# adapter_nucleo_f446re.net
KiCad netlist of a schematic drawn in EAGLE
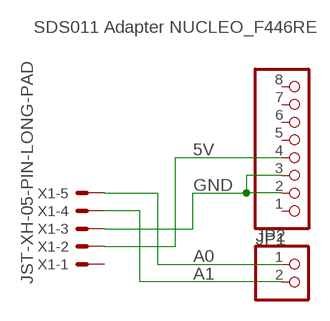
[diagram p0: schematic, sheet 1]

(export (version "E")
  (design (tool "Eeschema 10.0.6"))
  (components
    (comp (ref "JP1")
      (value "PINHD-1X8")
      (footprint "eagle-import:1X08")
      (libsource (lib "eagle-import") (part "PINHD-1X8"))
    )
    (comp (ref "JP2")
      (value "PINHD-1X2")
      (footprint "eagle-import:1X02")
      (libsource (lib "eagle-import") (part "PINHD-1X2"))
    )
    (comp (ref "X1")
      (value "JST-XH-05-PIN-LONG-PAD")
      (footprint "eagle-import:JST-XH-05-PACKAGE-LONG-PAD")
      (libsource (lib "eagle-import") (part "JST-XH-05-PIN-LONG-PAD"))
    )
  )
  (nets
    (net (code "1") (name "/5V") (class "Default")
      (node (ref "JP1") (pin "4") (pinfunction "4_4") (pintype "passive"))
      (node (ref "X1") (pin "2") (pinfunction "S_2") (pintype "passive"))
    )
    (net (code "2") (name "/A0") (class "Default")
      (node (ref "JP2") (pin "1") (pinfunction "1_1") (pintype "passive"))
      (node (ref "X1") (pin "5") (pinfunction "S_5") (pintype "passive"))
    )
    (net (code "3") (name "/A1") (class "Default")
      (node (ref "JP2") (pin "2") (pinfunction "2_2") (pintype "passive"))
      (node (ref "X1") (pin "4") (pinfunction "S_4") (pintype "passive"))
    )
    (net (code "4") (name "/GND") (class "Default")
      (node (ref "JP1") (pin "2") (pinfunction "2_2") (pintype "passive"))
      (node (ref "JP1") (pin "3") (pinfunction "3_3") (pintype "passive"))
      (node (ref "X1") (pin "3") (pinfunction "S_3") (pintype "passive"))
    )
    (net (code "5") (name "unconnected-(JP1-Pad1)") (class "Default")
      (node (ref "JP1") (pin "1") (pinfunction "1_1") (pintype "passive"))
    )
    (net (code "6") (name "unconnected-(JP1-Pad5)") (class "Default")
      (node (ref "JP1") (pin "5") (pinfunction "5_5") (pintype "passive"))
    )
    (net (code "7") (name "unconnected-(JP1-Pad6)") (class "Default")
      (node (ref "JP1") (pin "6") (pinfunction "6_6") (pintype "passive"))
    )
    (net (code "8") (name "unconnected-(JP1-Pad7)") (class "Default")
      (node (ref "JP1") (pin "7") (pinfunction "7_7") (pintype "passive"))
    )
    (net (code "9") (name "unconnected-(JP1-Pad8)") (class "Default")
      (node (ref "JP1") (pin "8") (pinfunction "8_8") (pintype "passive"))
    )
    (net (code "10") (name "unconnected-(X1A-S-Pad1)") (class "Default")
      (node (ref "X1") (pin "1") (pinfunction "S_1") (pintype "passive"))
    )
  )
)
